# ProPrj_USB_Hub_Port_PCB_2026-05-30.net
KiCad netlist of a schematic drawn in EasyEDA Pro
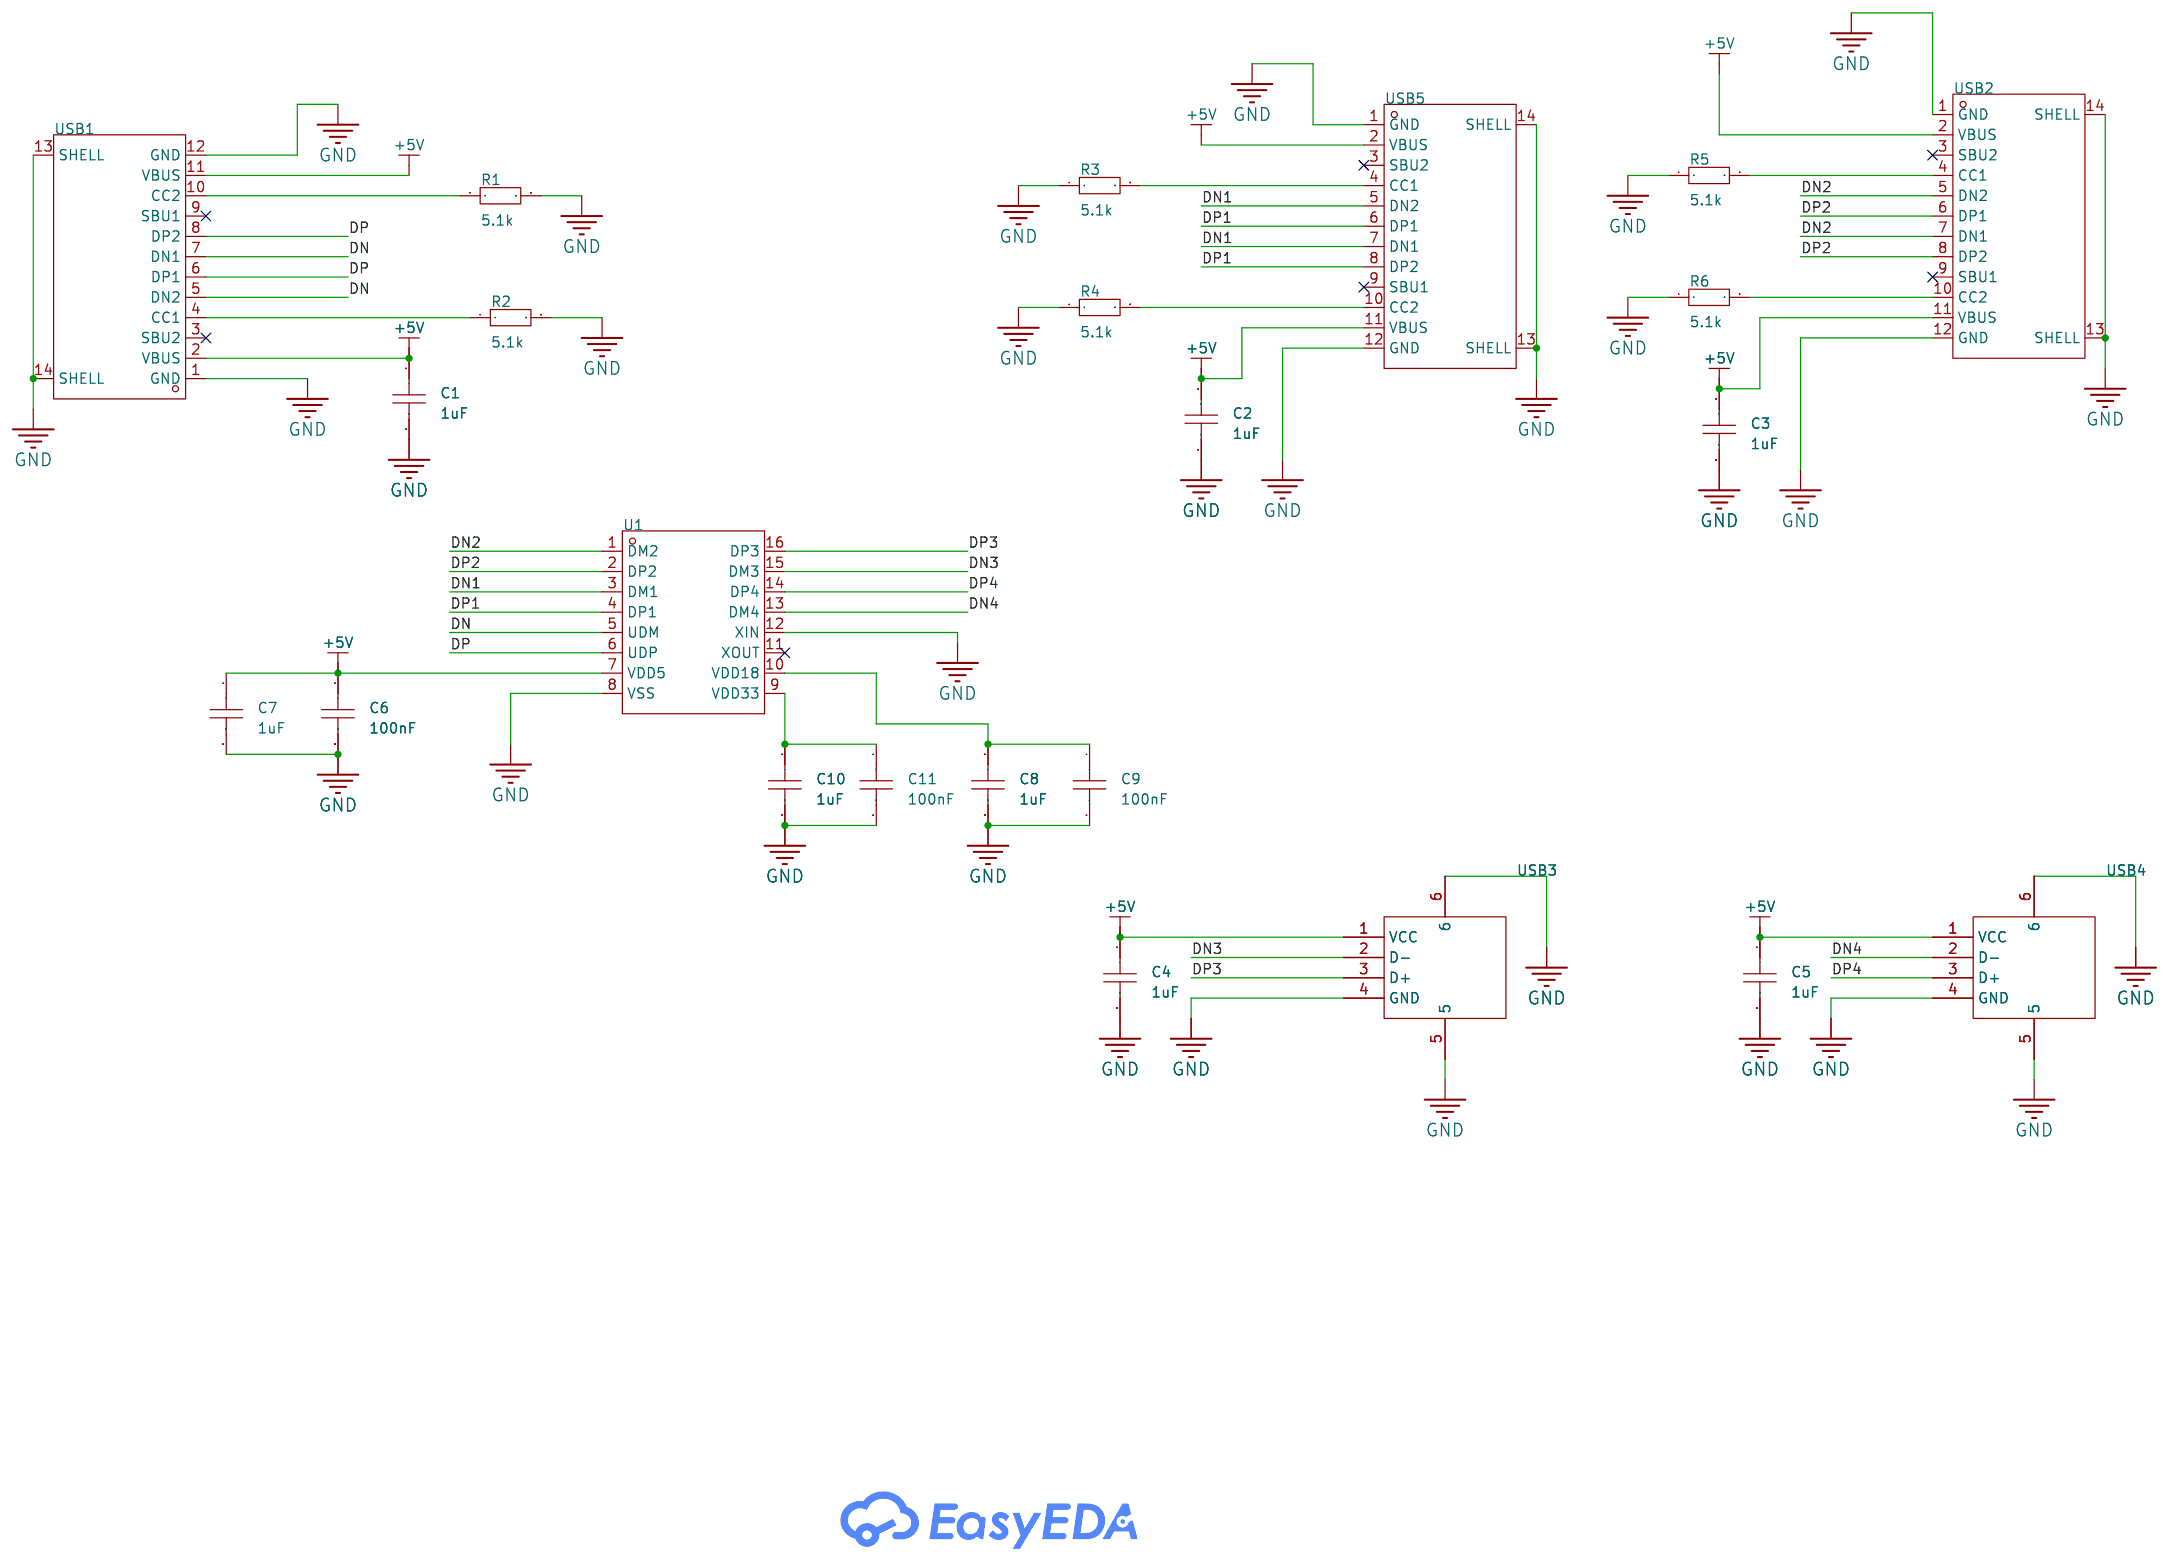
[diagram p0: schematic sheet]

(export (version "E")
  (design (tool "Eeschema 10.0.6"))
  (components
    (comp (ref "C1") (value "1uF") (footprint "easyedapro:C0603") (libsource (lib "easyedapro") (part "CAP")))
    (comp (ref "C2") (value "1uF") (footprint "easyedapro:C0603") (libsource (lib "easyedapro") (part "CAP")))
    (comp (ref "C3") (value "1uF") (footprint "easyedapro:C0603") (libsource (lib "easyedapro") (part "CAP")))
    (comp (ref "C4") (value "1uF") (footprint "easyedapro:C0603") (libsource (lib "easyedapro") (part "CAP")))
    (comp (ref "C5") (value "1uF") (footprint "easyedapro:C0603") (libsource (lib "easyedapro") (part "CAP")))
    (comp (ref "C6")
      (value "100nF")
      (footprint "easyedapro:C0603")
      (libsource (lib "easyedapro") (part "CAP"))
    )
    (comp (ref "C7") (value "1uF") (footprint "easyedapro:C0603") (libsource (lib "easyedapro") (part "CAP")))
    (comp (ref "C8") (value "1uF") (footprint "easyedapro:C0603") (libsource (lib "easyedapro") (part "CAP")))
    (comp (ref "C9")
      (value "100nF")
      (footprint "easyedapro:C0603")
      (libsource (lib "easyedapro") (part "CAP"))
    )
    (comp (ref "C10")
      (value "1uF")
      (footprint "easyedapro:C0603")
      (libsource (lib "easyedapro") (part "CAP"))
    )
    (comp (ref "C11")
      (value "100nF")
      (footprint "easyedapro:C0603")
      (libsource (lib "easyedapro") (part "CAP"))
    )
    (comp (ref "R1")
      (value "5.1k")
      (footprint "easyedapro:R0603")
      (libsource (lib "easyedapro") (part "Res"))
    )
    (comp (ref "R2")
      (value "5.1k")
      (footprint "easyedapro:R0603")
      (libsource (lib "easyedapro") (part "Res"))
    )
    (comp (ref "R3")
      (value "5.1k")
      (footprint "easyedapro:R0603")
      (libsource (lib "easyedapro") (part "Res"))
    )
    (comp (ref "R4")
      (value "5.1k")
      (footprint "easyedapro:R0603")
      (libsource (lib "easyedapro") (part "Res"))
    )
    (comp (ref "R5")
      (value "5.1k")
      (footprint "easyedapro:R0603")
      (libsource (lib "easyedapro") (part "Res"))
    )
    (comp (ref "R6")
      (value "5.1k")
      (footprint "easyedapro:R0603")
      (libsource (lib "easyedapro") (part "Res"))
    )
    (comp (ref "U1")
      (value "SL2.1s")
      (footprint "easyedapro:SSOP-16_L4.6-W2.6-P0.53-LS4.0-BL")
      (fields (field (name "Manufacturer") "CoreChips(和芯润德)"))
      (libsource (lib "easyedapro") (part "SL2.1S"))
    )
    (comp (ref "USB1")
      (value "TYPE-C 16PIN 2MD(073)")
      (footprint "easyedapro:USB-C-SMD_TYPE-C-6PIN-2MD-073")
      (fields (field (name "Manufacturer") "SHOU HAN(首韩)"))
      (libsource (lib "easyedapro") (part "TYPE-C 16PIN 2MD(073)"))
    )
    (comp (ref "USB2")
      (value "TYPE-C 16PIN 2MD(073)")
      (footprint "easyedapro:USB-C-SMD_TYPE-C-6PIN-2MD-073")
      (fields (field (name "Manufacturer") "SHOU HAN(首韩)"))
      (libsource (lib "easyedapro") (part "TYPE-C 16PIN 2MD(073)"))
    )
    (comp (ref "USB3")
      (value "10.0 QHHTZB6.3")
      (footprint "easyedapro:USB-A-TH_10.0QHHTZB6.3")
      (fields (field (name "Manufacturer") "SHOU HAN(首韩)"))
      (libsource (lib "easyedapro") (part "10.0 QHHTZB6.3"))
    )
    (comp (ref "USB4")
      (value "10.0 QHHTZB6.3")
      (footprint "easyedapro:USB-A-TH_10.0QHHTZB6.3")
      (fields (field (name "Manufacturer") "SHOU HAN(首韩)"))
      (libsource (lib "easyedapro") (part "10.0 QHHTZB6.3"))
    )
    (comp (ref "USB5")
      (value "TYPE-C 16PIN 2MD(073)")
      (footprint "easyedapro:USB-C-SMD_TYPE-C-6PIN-2MD-073")
      (fields (field (name "Manufacturer") "SHOU HAN(首韩)"))
      (libsource (lib "easyedapro") (part "TYPE-C 16PIN 2MD(073)"))
    )
  )
  (nets
    (net (code "1") (name "+5V") (class "Default")
      (node (ref "C1") (pin "1") (pinfunction "1_1") (pintype "input"))
      (node (ref "C2") (pin "1") (pinfunction "1_1") (pintype "input"))
      (node (ref "C3") (pin "1") (pinfunction "1_1") (pintype "input"))
      (node (ref "C4") (pin "1") (pinfunction "1_1") (pintype "input"))
      (node (ref "C5") (pin "1") (pinfunction "1_1") (pintype "input"))
      (node (ref "C6") (pin "1") (pinfunction "1_1") (pintype "input"))
      (node (ref "C7") (pin "1") (pinfunction "1_1") (pintype "input"))
      (node (ref "U1") (pin "7") (pinfunction "VDD5_7") (pintype "unspecified"))
      (node (ref "USB1") (pin "11") (pinfunction "VBUS_11") (pintype "unspecified"))
      (node (ref "USB1") (pin "2") (pinfunction "VBUS_2") (pintype "unspecified"))
      (node (ref "USB2") (pin "11") (pinfunction "VBUS_11") (pintype "unspecified"))
      (node (ref "USB2") (pin "2") (pinfunction "VBUS_2") (pintype "unspecified"))
      (node (ref "USB3") (pin "1") (pinfunction "VCC_1") (pintype "unspecified"))
      (node (ref "USB4") (pin "1") (pinfunction "VCC_1") (pintype "unspecified"))
      (node (ref "USB5") (pin "11") (pinfunction "VBUS_11") (pintype "unspecified"))
      (node (ref "USB5") (pin "2") (pinfunction "VBUS_2") (pintype "unspecified"))
    )
    (net (code "2") (name "/DN") (class "Default")
      (node (ref "U1") (pin "5") (pinfunction "UDM_5") (pintype "unspecified"))
      (node (ref "USB1") (pin "5") (pinfunction "DN2_5") (pintype "unspecified"))
      (node (ref "USB1") (pin "7") (pinfunction "DN1_7") (pintype "unspecified"))
    )
    (net (code "3") (name "/DN1") (class "Default")
      (node (ref "U1") (pin "3") (pinfunction "DM1_3") (pintype "unspecified"))
      (node (ref "USB5") (pin "5") (pinfunction "DN2_5") (pintype "unspecified"))
      (node (ref "USB5") (pin "7") (pinfunction "DN1_7") (pintype "unspecified"))
    )
    (net (code "4") (name "/DN2") (class "Default")
      (node (ref "U1") (pin "1") (pinfunction "DM2_1") (pintype "unspecified"))
      (node (ref "USB2") (pin "5") (pinfunction "DN2_5") (pintype "unspecified"))
      (node (ref "USB2") (pin "7") (pinfunction "DN1_7") (pintype "unspecified"))
    )
    (net (code "5") (name "/DN3") (class "Default")
      (node (ref "U1") (pin "15") (pinfunction "DM3_15") (pintype "unspecified"))
      (node (ref "USB3") (pin "2") (pinfunction "D-_2") (pintype "unspecified"))
    )
    (net (code "6") (name "/DN4") (class "Default")
      (node (ref "U1") (pin "13") (pinfunction "DM4_13") (pintype "unspecified"))
      (node (ref "USB4") (pin "2") (pinfunction "D-_2") (pintype "unspecified"))
    )
    (net (code "7") (name "/DP") (class "Default")
      (node (ref "U1") (pin "6") (pinfunction "UDP_6") (pintype "unspecified"))
      (node (ref "USB1") (pin "6") (pinfunction "DP1_6") (pintype "unspecified"))
      (node (ref "USB1") (pin "8") (pinfunction "DP2_8") (pintype "unspecified"))
    )
    (net (code "8") (name "/DP1") (class "Default")
      (node (ref "U1") (pin "4") (pinfunction "DP1_4") (pintype "unspecified"))
      (node (ref "USB5") (pin "6") (pinfunction "DP1_6") (pintype "unspecified"))
      (node (ref "USB5") (pin "8") (pinfunction "DP2_8") (pintype "unspecified"))
    )
    (net (code "9") (name "/DP2") (class "Default")
      (node (ref "U1") (pin "2") (pinfunction "DP2_2") (pintype "unspecified"))
      (node (ref "USB2") (pin "6") (pinfunction "DP1_6") (pintype "unspecified"))
      (node (ref "USB2") (pin "8") (pinfunction "DP2_8") (pintype "unspecified"))
    )
    (net (code "10") (name "/DP3") (class "Default")
      (node (ref "U1") (pin "16") (pinfunction "DP3_16") (pintype "unspecified"))
      (node (ref "USB3") (pin "3") (pinfunction "D+_3") (pintype "unspecified"))
    )
    (net (code "11") (name "/DP4") (class "Default")
      (node (ref "U1") (pin "14") (pinfunction "DP4_14") (pintype "unspecified"))
      (node (ref "USB4") (pin "3") (pinfunction "D+_3") (pintype "unspecified"))
    )
    (net (code "12") (name "GND") (class "Default")
      (node (ref "C1") (pin "2") (pinfunction "2_2") (pintype "input"))
      (node (ref "C10") (pin "2") (pinfunction "2_2") (pintype "input"))
      (node (ref "C11") (pin "2") (pinfunction "2_2") (pintype "input"))
      (node (ref "C2") (pin "2") (pinfunction "2_2") (pintype "input"))
      (node (ref "C3") (pin "2") (pinfunction "2_2") (pintype "input"))
      (node (ref "C4") (pin "2") (pinfunction "2_2") (pintype "input"))
      (node (ref "C5") (pin "2") (pinfunction "2_2") (pintype "input"))
      (node (ref "C6") (pin "2") (pinfunction "2_2") (pintype "input"))
      (node (ref "C7") (pin "2") (pinfunction "2_2") (pintype "input"))
      (node (ref "C8") (pin "2") (pinfunction "2_2") (pintype "input"))
      (node (ref "C9") (pin "2") (pinfunction "2_2") (pintype "input"))
      (node (ref "R1") (pin "2") (pinfunction "2_2") (pintype "input"))
      (node (ref "R2") (pin "2") (pinfunction "2_2") (pintype "input"))
      (node (ref "R3") (pin "1") (pinfunction "1_1") (pintype "input"))
      (node (ref "R4") (pin "1") (pinfunction "1_1") (pintype "input"))
      (node (ref "R5") (pin "1") (pinfunction "1_1") (pintype "input"))
      (node (ref "R6") (pin "1") (pinfunction "1_1") (pintype "input"))
      (node (ref "U1") (pin "12") (pinfunction "XIN_12") (pintype "unspecified"))
      (node (ref "U1") (pin "8") (pinfunction "VSS_8") (pintype "unspecified"))
      (node (ref "USB1") (pin "1") (pinfunction "GND_1") (pintype "unspecified"))
      (node (ref "USB1") (pin "12") (pinfunction "GND_12") (pintype "unspecified"))
      (node (ref "USB1") (pin "13") (pinfunction "SHELL_13") (pintype "unspecified"))
      (node (ref "USB1") (pin "14") (pinfunction "SHELL_14") (pintype "unspecified"))
      (node (ref "USB2") (pin "1") (pinfunction "GND_1") (pintype "unspecified"))
      (node (ref "USB2") (pin "12") (pinfunction "GND_12") (pintype "unspecified"))
      (node (ref "USB2") (pin "13") (pinfunction "SHELL_13") (pintype "unspecified"))
      (node (ref "USB2") (pin "14") (pinfunction "SHELL_14") (pintype "unspecified"))
      (node (ref "USB3") (pin "4") (pinfunction "GND_4") (pintype "unspecified"))
      (node (ref "USB3") (pin "5") (pinfunction "5_5") (pintype "unspecified"))
      (node (ref "USB3") (pin "6") (pinfunction "6_6") (pintype "unspecified"))
      (node (ref "USB4") (pin "4") (pinfunction "GND_4") (pintype "unspecified"))
      (node (ref "USB4") (pin "5") (pinfunction "5_5") (pintype "unspecified"))
      (node (ref "USB4") (pin "6") (pinfunction "6_6") (pintype "unspecified"))
      (node (ref "USB5") (pin "1") (pinfunction "GND_1") (pintype "unspecified"))
      (node (ref "USB5") (pin "12") (pinfunction "GND_12") (pintype "unspecified"))
      (node (ref "USB5") (pin "13") (pinfunction "SHELL_13") (pintype "unspecified"))
      (node (ref "USB5") (pin "14") (pinfunction "SHELL_14") (pintype "unspecified"))
    )
    (net (code "13") (name "Net-(U1-VDD18)") (class "Default")
      (node (ref "C8") (pin "1") (pinfunction "1_1") (pintype "input"))
      (node (ref "C9") (pin "1") (pinfunction "1_1") (pintype "input"))
      (node (ref "U1") (pin "10") (pinfunction "VDD18_10") (pintype "unspecified"))
    )
    (net (code "14") (name "Net-(U1-VDD33)") (class "Default")
      (node (ref "C10") (pin "1") (pinfunction "1_1") (pintype "input"))
      (node (ref "C11") (pin "1") (pinfunction "1_1") (pintype "input"))
      (node (ref "U1") (pin "9") (pinfunction "VDD33_9") (pintype "unspecified"))
    )
    (net (code "15") (name "Net-(USB1-CC1)") (class "Default")
      (node (ref "R2") (pin "1") (pinfunction "1_1") (pintype "input"))
      (node (ref "USB1") (pin "4") (pinfunction "CC1_4") (pintype "unspecified"))
    )
    (net (code "16") (name "Net-(USB1-CC2)") (class "Default")
      (node (ref "R1") (pin "1") (pinfunction "1_1") (pintype "input"))
      (node (ref "USB1") (pin "10") (pinfunction "CC2_10") (pintype "unspecified"))
    )
    (net (code "17") (name "Net-(USB2-CC1)") (class "Default")
      (node (ref "R5") (pin "2") (pinfunction "2_2") (pintype "input"))
      (node (ref "USB2") (pin "4") (pinfunction "CC1_4") (pintype "unspecified"))
    )
    (net (code "18") (name "Net-(USB2-CC2)") (class "Default")
      (node (ref "R6") (pin "2") (pinfunction "2_2") (pintype "input"))
      (node (ref "USB2") (pin "10") (pinfunction "CC2_10") (pintype "unspecified"))
    )
    (net (code "19") (name "Net-(USB5-CC1)") (class "Default")
      (node (ref "R3") (pin "2") (pinfunction "2_2") (pintype "input"))
      (node (ref "USB5") (pin "4") (pinfunction "CC1_4") (pintype "unspecified"))
    )
    (net (code "20") (name "Net-(USB5-CC2)") (class "Default")
      (node (ref "R4") (pin "2") (pinfunction "2_2") (pintype "input"))
      (node (ref "USB5") (pin "10") (pinfunction "CC2_10") (pintype "unspecified"))
    )
    (net (code "21") (name "unconnected-(U1-XOUT-Pad11)") (class "Default")
      (node (ref "U1") (pin "11") (pinfunction "XOUT_11") (pintype "unspecified+no_connect"))
    )
    (net (code "22") (name "unconnected-(USB1-SBU1-Pad9)") (class "Default")
      (node (ref "USB1") (pin "9") (pinfunction "SBU1_9") (pintype "unspecified+no_connect"))
    )
    (net (code "23") (name "unconnected-(USB1-SBU2-Pad3)") (class "Default")
      (node (ref "USB1") (pin "3") (pinfunction "SBU2_3") (pintype "unspecified+no_connect"))
    )
    (net (code "24") (name "unconnected-(USB2-SBU1-Pad9)") (class "Default")
      (node (ref "USB2") (pin "9") (pinfunction "SBU1_9") (pintype "unspecified+no_connect"))
    )
    (net (code "25") (name "unconnected-(USB2-SBU2-Pad3)") (class "Default")
      (node (ref "USB2") (pin "3") (pinfunction "SBU2_3") (pintype "unspecified+no_connect"))
    )
    (net (code "26") (name "unconnected-(USB5-SBU1-Pad9)") (class "Default")
      (node (ref "USB5") (pin "9") (pinfunction "SBU1_9") (pintype "unspecified+no_connect"))
    )
    (net (code "27") (name "unconnected-(USB5-SBU2-Pad3)") (class "Default")
      (node (ref "USB5") (pin "3") (pinfunction "SBU2_3") (pintype "unspecified+no_connect"))
    )
  )
)
